# ISP.net
KiCad netlist of a schematic drawn in EAGLE
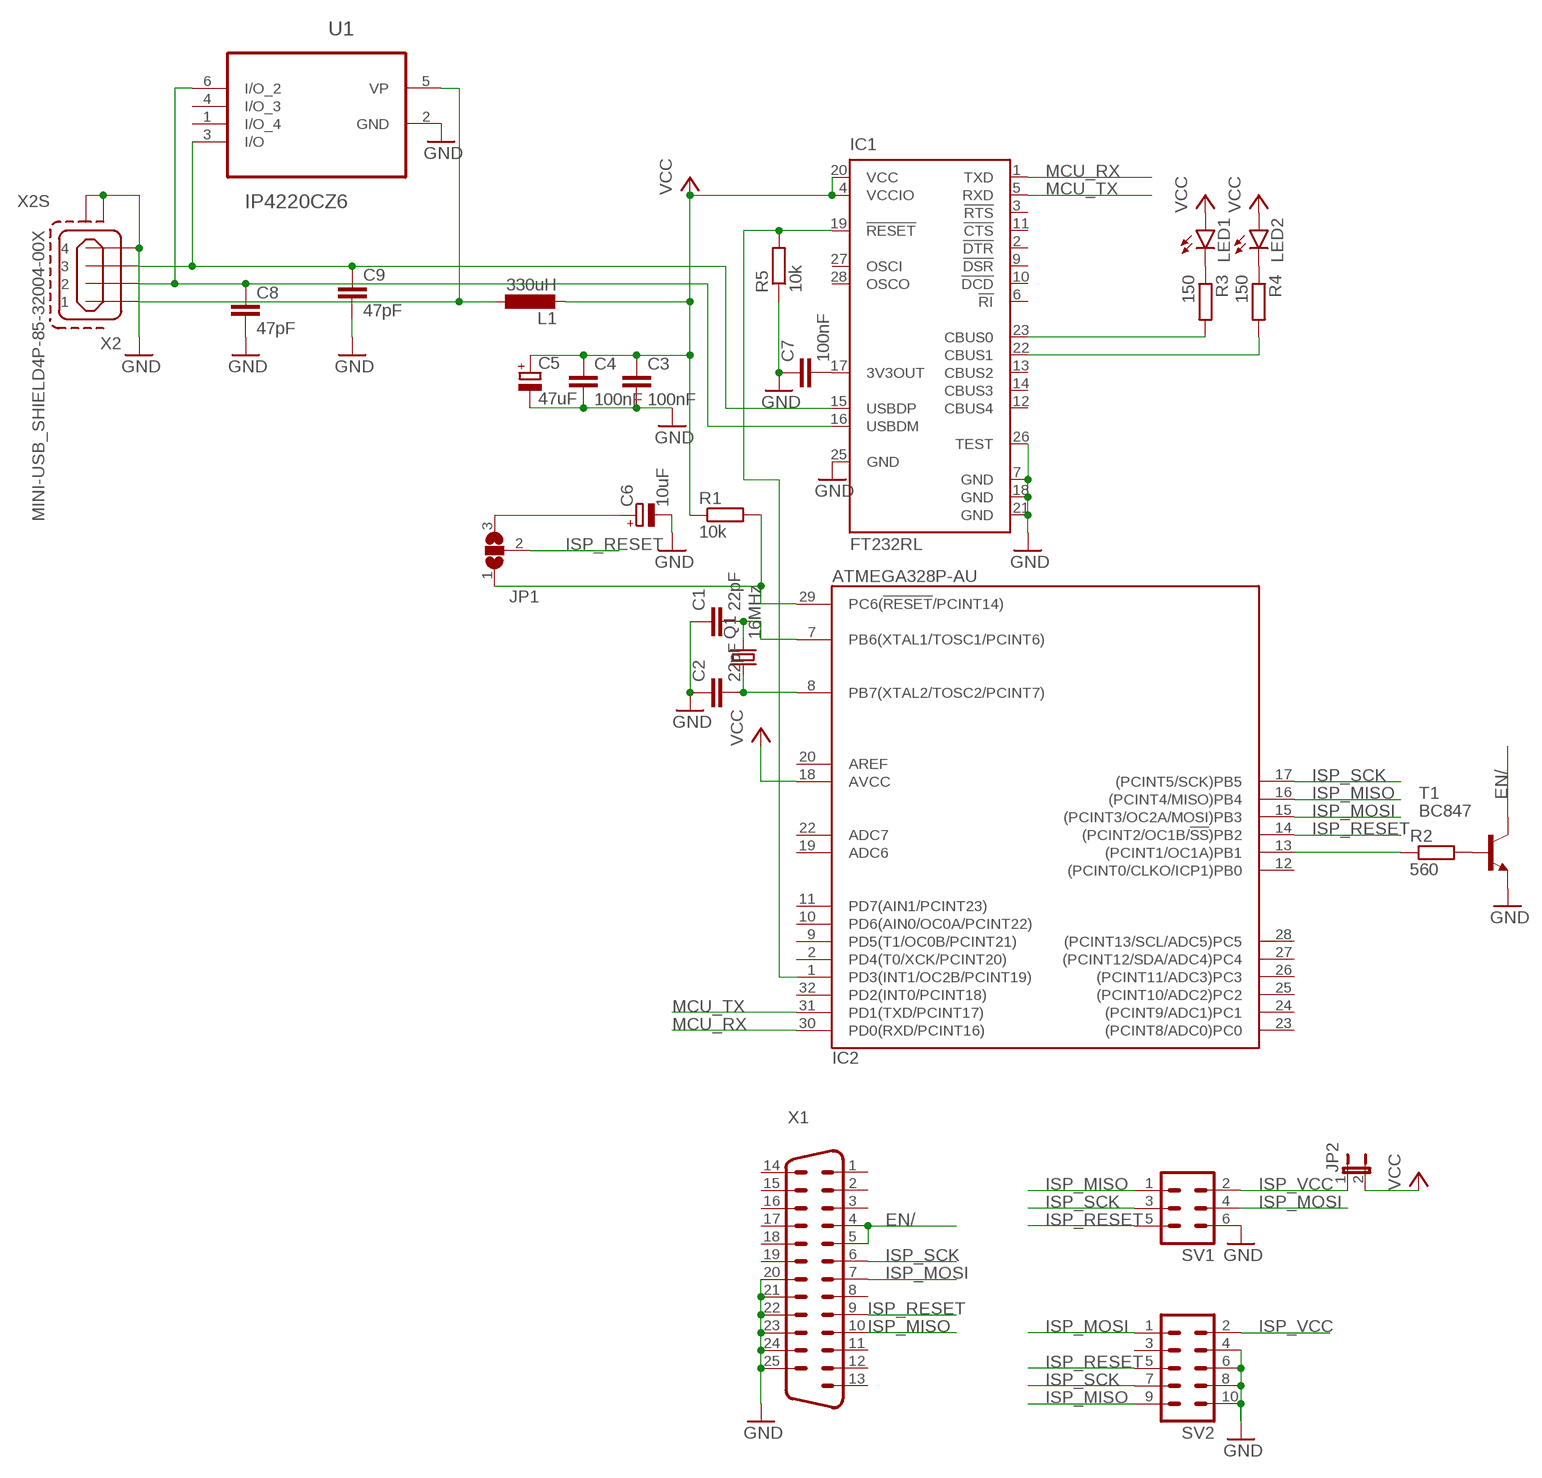
[diagram p0: schematic, sheet 1]

(export (version "E")
  (design (tool "Eeschema 10.0.6"))
  (components
    (comp (ref "C1")
      (value "22pF")
      (footprint "eagle-import:C0805")
      (libsource (lib "eagle-import") (part "C-EUC0805"))
    )
    (comp (ref "C2")
      (value "22pF")
      (footprint "eagle-import:C0805")
      (libsource (lib "eagle-import") (part "C-EUC0805"))
    )
    (comp (ref "C3")
      (value "100nF")
      (footprint "eagle-import:C0805")
      (libsource (lib "eagle-import") (part "C-EUC0805"))
    )
    (comp (ref "C4")
      (value "100nF")
      (footprint "eagle-import:C0805")
      (libsource (lib "eagle-import") (part "C-EUC0805"))
    )
    (comp (ref "C5")
      (value "47uF")
      (footprint "eagle-import:PANASONIC_D")
      (libsource (lib "eagle-import") (part "CPOL-EUD"))
    )
    (comp (ref "C6")
      (value "10uF")
      (footprint "eagle-import:PANASONIC_C")
      (libsource (lib "eagle-import") (part "CPOL-EUC"))
    )
    (comp (ref "C7")
      (value "100nF")
      (footprint "eagle-import:C0805")
      (libsource (lib "eagle-import") (part "C-EUC0805"))
    )
    (comp (ref "C8")
      (value "47pF")
      (footprint "eagle-import:C0805")
      (libsource (lib "eagle-import") (part "C-EUC0805"))
    )
    (comp (ref "C9")
      (value "47pF")
      (footprint "eagle-import:C0805")
      (libsource (lib "eagle-import") (part "C-EUC0805"))
    )
    (comp (ref "IC1")
      (value "FT232RL")
      (footprint "eagle-import:SSOP28")
      (libsource (lib "eagle-import") (part "FT232RL"))
    )
    (comp (ref "IC2")
      (value "ATMEGA328P-AU")
      (footprint "eagle-import:QFP32_7X7_0.80")
      (libsource (lib "eagle-import") (part "ATMEGA8P-AU32"))
    )
    (comp (ref "JP1")
      (value "SJ2W")
      (footprint "eagle-import:SJ_2")
      (libsource (lib "eagle-import") (part "SJ2W"))
    )
    (comp (ref "JP2")
      (value "JP1E")
      (footprint "eagle-import:JP1")
      (libsource (lib "eagle-import") (part "JP1E"))
    )
    (comp (ref "L1")
      (value "330uH")
      (footprint "eagle-import:L1812")
      (libsource (lib "eagle-import") (part "L-EUL1812"))
    )
    (comp (ref "LED1")
      (value "LEDCHIPLED_1206")
      (footprint "eagle-import:CHIPLED_1206")
      (libsource (lib "eagle-import") (part "LEDCHIPLED_1206"))
    )
    (comp (ref "LED2")
      (value "LEDCHIPLED_1206")
      (footprint "eagle-import:CHIPLED_1206")
      (libsource (lib "eagle-import") (part "LEDCHIPLED_1206"))
    )
    (comp (ref "Q1")
      (value "16MHz")
      (footprint "eagle-import:HC49UP")
      (libsource (lib "eagle-import") (part "CRYSTALHC49UP"))
    )
    (comp (ref "R1")
      (value "10k")
      (footprint "eagle-import:R0805")
      (libsource (lib "eagle-import") (part "R-EU_R0805"))
    )
    (comp (ref "R2")
      (value "560")
      (footprint "eagle-import:R0805")
      (libsource (lib "eagle-import") (part "R-EU_R0805"))
    )
    (comp (ref "R3")
      (value "150")
      (footprint "eagle-import:R0805")
      (libsource (lib "eagle-import") (part "R-EU_R0805"))
    )
    (comp (ref "R4")
      (value "150")
      (footprint "eagle-import:R0805")
      (libsource (lib "eagle-import") (part "R-EU_R0805"))
    )
    (comp (ref "R5")
      (value "10k")
      (footprint "eagle-import:R0805")
      (libsource (lib "eagle-import") (part "R-EU_R0805"))
    )
    (comp (ref "SV1")
      (value "ML6")
      (footprint "eagle-import:ML6")
      (libsource (lib "eagle-import") (part "ML6"))
    )
    (comp (ref "SV2")
      (value "ML10")
      (footprint "eagle-import:ML10")
      (libsource (lib "eagle-import") (part "ML10"))
    )
    (comp (ref "T1")
      (value "BC847")
      (footprint "eagle-import:SOT23")
      (libsource (lib "eagle-import") (part "BC847"))
    )
    (comp (ref "U1")
      (value "IP4220CZ6")
      (footprint "eagle-import:SOT95P275X110-6N")
      (libsource (lib "eagle-import") (part "IP4220CZ6"))
    )
    (comp (ref "X1")
      (value "M25HP")
      (footprint "eagle-import:M25HP")
      (libsource (lib "eagle-import") (part "M25HP"))
    )
    (comp (ref "X2")
      (value "MINI-USB_SHIELD4P-85-32004-00X")
      (footprint "eagle-import:85-32004-00X")
      (libsource (lib "eagle-import") (part "MINI-USB_SHIELD4P-85-32004-00X"))
    )
  )
  (nets
    (net (code "1") (name "/EN{slash}") (class "Default")
      (node (ref "T1") (pin "3") (pinfunction "C_3") (pintype "passive"))
      (node (ref "X1") (pin "4") (pinfunction "4_4") (pintype "passive"))
      (node (ref "X1") (pin "5") (pinfunction "5_5") (pintype "passive"))
    )
    (net (code "2") (name "/ISP_MISO") (class "Default")
      (node (ref "IC2") (pin "16") (pinfunction "(PCINT4/MISO)PB4_16") (pintype "bidirectional"))
      (node (ref "SV1") (pin "1") (pinfunction "1_1") (pintype "passive"))
      (node (ref "SV2") (pin "9") (pinfunction "9_9") (pintype "passive"))
      (node (ref "X1") (pin "10") (pinfunction "10_10") (pintype "passive"))
    )
    (net (code "3") (name "/ISP_MOSI") (class "Default")
      (node (ref "IC2") (pin "15") (pinfunction "(PCINT3/OC2A/MOSI)PB3_15") (pintype "bidirectional"))
      (node (ref "SV1") (pin "4") (pinfunction "4_4") (pintype "passive"))
      (node (ref "SV2") (pin "1") (pinfunction "1_1") (pintype "passive"))
      (node (ref "X1") (pin "7") (pinfunction "7_7") (pintype "passive"))
    )
    (net (code "4") (name "/ISP_RESET") (class "Default")
      (node (ref "IC2") (pin "14") (pinfunction "(PCINT2/OC1B/~{SS})PB2_14") (pintype "bidirectional"))
      (node (ref "JP1") (pin "2") (pinfunction "2_2") (pintype "passive"))
      (node (ref "SV1") (pin "5") (pinfunction "5_5") (pintype "passive"))
      (node (ref "SV2") (pin "5") (pinfunction "5_5") (pintype "passive"))
      (node (ref "X1") (pin "9") (pinfunction "9_9") (pintype "passive"))
    )
    (net (code "5") (name "/ISP_SCK") (class "Default")
      (node (ref "IC2") (pin "17") (pinfunction "(PCINT5/SCK)PB5_17") (pintype "bidirectional"))
      (node (ref "SV1") (pin "3") (pinfunction "3_3") (pintype "passive"))
      (node (ref "SV2") (pin "7") (pinfunction "7_7") (pintype "passive"))
      (node (ref "X1") (pin "6") (pinfunction "6_6") (pintype "passive"))
    )
    (net (code "6") (name "/ISP_VCC") (class "Default")
      (node (ref "JP2") (pin "1") (pinfunction "1_1") (pintype "passive"))
      (node (ref "SV1") (pin "2") (pinfunction "2_2") (pintype "passive"))
      (node (ref "SV2") (pin "2") (pinfunction "2_2") (pintype "passive"))
    )
    (net (code "7") (name "/MCU_RX") (class "Default")
      (node (ref "IC1") (pin "1") (pinfunction "TXD_1") (pintype "output"))
      (node (ref "IC2") (pin "30") (pinfunction "PD0(RXD/PCINT16)_30") (pintype "bidirectional"))
    )
    (net (code "8") (name "/MCU_TX") (class "Default")
      (node (ref "IC1") (pin "5") (pinfunction "RXD_5") (pintype "input"))
      (node (ref "IC2") (pin "31") (pinfunction "PD1(TXD/PCINT17)_31") (pintype "bidirectional"))
    )
    (net (code "9") (name "GND") (class "Default")
      (node (ref "C1") (pin "1") (pinfunction "1_1") (pintype "passive"))
      (node (ref "C2") (pin "1") (pinfunction "1_1") (pintype "passive"))
      (node (ref "C3") (pin "2") (pinfunction "2_2") (pintype "passive"))
      (node (ref "C4") (pin "2") (pinfunction "2_2") (pintype "passive"))
      (node (ref "C5") (pin "-") (pinfunction "-_-") (pintype "passive"))
      (node (ref "C6") (pin "-") (pinfunction "-_-") (pintype "passive"))
      (node (ref "C7") (pin "1") (pinfunction "1_1") (pintype "passive"))
      (node (ref "C8") (pin "2") (pinfunction "2_2") (pintype "passive"))
      (node (ref "C9") (pin "2") (pinfunction "2_2") (pintype "passive"))
      (node (ref "IC1") (pin "18") (pinfunction "GND_18") (pintype "power_in"))
      (node (ref "IC1") (pin "21") (pinfunction "GND_21") (pintype "power_in"))
      (node (ref "IC1") (pin "25") (pinfunction "GND_25") (pintype "power_in"))
      (node (ref "IC1") (pin "26") (pinfunction "TEST_26") (pintype "input"))
      (node (ref "IC1") (pin "7") (pinfunction "GND_7") (pintype "power_in"))
      (node (ref "R5") (pin "1") (pinfunction "1_1") (pintype "passive"))
      (node (ref "SV1") (pin "6") (pinfunction "6_6") (pintype "passive"))
      (node (ref "SV2") (pin "10") (pinfunction "10_10") (pintype "passive"))
      (node (ref "SV2") (pin "4") (pinfunction "4_4") (pintype "passive"))
      (node (ref "SV2") (pin "6") (pinfunction "6_6") (pintype "passive"))
      (node (ref "SV2") (pin "8") (pinfunction "8_8") (pintype "passive"))
      (node (ref "T1") (pin "2") (pinfunction "E_2") (pintype "passive"))
      (node (ref "U1") (pin "2") (pinfunction "GND_2") (pintype "passive"))
      (node (ref "X1") (pin "20") (pinfunction "20_20") (pintype "passive"))
      (node (ref "X1") (pin "21") (pinfunction "21_21") (pintype "passive"))
      (node (ref "X1") (pin "22") (pinfunction "22_22") (pintype "passive"))
      (node (ref "X1") (pin "23") (pinfunction "23_23") (pintype "passive"))
      (node (ref "X1") (pin "24") (pinfunction "24_24") (pintype "passive"))
      (node (ref "X1") (pin "25") (pinfunction "25_25") (pintype "passive"))
      (node (ref "X2") (pin "4") (pinfunction "4_4") (pintype "passive"))
      (node (ref "X2") (pin "M1") (pinfunction "S1_M1") (pintype "passive"))
      (node (ref "X2") (pin "M2") (pinfunction "S2_M2") (pintype "passive"))
    )
    (net (code "10") (name "Net-(C6-Pad+)") (class "Default")
      (node (ref "C6") (pin "+") (pinfunction "+_+") (pintype "passive"))
      (node (ref "JP1") (pin "3") (pinfunction "3_3") (pintype "passive"))
    )
    (net (code "11") (name "Net-(IC1-3V3OUT)") (class "Default")
      (node (ref "C7") (pin "2") (pinfunction "2_2") (pintype "passive"))
      (node (ref "IC1") (pin "17") (pinfunction "3V3OUT_17") (pintype "output"))
    )
    (net (code "12") (name "Net-(IC1-CBUS0)") (class "Default")
      (node (ref "IC1") (pin "23") (pinfunction "CBUS0_23") (pintype "bidirectional"))
      (node (ref "R3") (pin "2") (pinfunction "2_2") (pintype "passive"))
    )
    (net (code "13") (name "Net-(IC1-CBUS1)") (class "Default")
      (node (ref "IC1") (pin "22") (pinfunction "CBUS1_22") (pintype "bidirectional"))
      (node (ref "R4") (pin "2") (pinfunction "2_2") (pintype "passive"))
    )
    (net (code "14") (name "Net-(IC1-USBDM)") (class "Default")
      (node (ref "C8") (pin "1") (pinfunction "1_1") (pintype "passive"))
      (node (ref "IC1") (pin "16") (pinfunction "USBDM_16") (pintype "bidirectional"))
      (node (ref "U1") (pin "6") (pinfunction "I/O_2_6") (pintype "bidirectional"))
      (node (ref "X2") (pin "2") (pinfunction "2_2") (pintype "passive"))
    )
    (net (code "15") (name "Net-(IC1-USBDP)") (class "Default")
      (node (ref "C9") (pin "1") (pinfunction "1_1") (pintype "passive"))
      (node (ref "IC1") (pin "15") (pinfunction "USBDP_15") (pintype "bidirectional"))
      (node (ref "U1") (pin "3") (pinfunction "I/O_3") (pintype "bidirectional"))
      (node (ref "X2") (pin "3") (pinfunction "3_3") (pintype "passive"))
    )
    (net (code "16") (name "Net-(IC1-~{RESET})") (class "Default")
      (node (ref "IC1") (pin "19") (pinfunction "~{RESET}_19") (pintype "input"))
      (node (ref "IC2") (pin "1") (pinfunction "PD3(INT1/OC2B/PCINT19)_1") (pintype "bidirectional"))
      (node (ref "R5") (pin "2") (pinfunction "2_2") (pintype "passive"))
    )
    (net (code "17") (name "Net-(IC2A-(PCINT1{slash}OC1A)PB1)") (class "Default")
      (node (ref "IC2") (pin "13") (pinfunction "(PCINT1/OC1A)PB1_13") (pintype "bidirectional"))
      (node (ref "R2") (pin "1") (pinfunction "1_1") (pintype "passive"))
    )
    (net (code "18") (name "Net-(IC2A-PB6(XTAL1{slash}TOSC1{slash}PCINT6))") (class "Default")
      (node (ref "C1") (pin "2") (pinfunction "2_2") (pintype "passive"))
      (node (ref "IC2") (pin "7") (pinfunction "PB6(XTAL1/TOSC1/PCINT6)_7") (pintype "bidirectional"))
      (node (ref "Q1") (pin "2") (pinfunction "2_2") (pintype "passive"))
    )
    (net (code "19") (name "Net-(IC2A-PB7(XTAL2{slash}TOSC2{slash}PCINT7))") (class "Default")
      (node (ref "C2") (pin "2") (pinfunction "2_2") (pintype "passive"))
      (node (ref "IC2") (pin "8") (pinfunction "PB7(XTAL2/TOSC2/PCINT7)_8") (pintype "bidirectional"))
      (node (ref "Q1") (pin "1") (pinfunction "1_1") (pintype "passive"))
    )
    (net (code "20") (name "Net-(IC2A-PC6(~{RESET}{slash}PCINT14))") (class "Default")
      (node (ref "IC2") (pin "29") (pinfunction "PC6(~{RESET}/PCINT14)_29") (pintype "bidirectional"))
      (node (ref "JP1") (pin "1") (pinfunction "1_1") (pintype "passive"))
      (node (ref "R1") (pin "2") (pinfunction "2_2") (pintype "passive"))
    )
    (net (code "21") (name "Net-(LED1-PadC)") (class "Default")
      (node (ref "LED1") (pin "C") (pinfunction "C_C") (pintype "passive"))
      (node (ref "R3") (pin "1") (pinfunction "1_1") (pintype "passive"))
    )
    (net (code "22") (name "Net-(LED2-PadC)") (class "Default")
      (node (ref "LED2") (pin "C") (pinfunction "C_C") (pintype "passive"))
      (node (ref "R4") (pin "1") (pinfunction "1_1") (pintype "passive"))
    )
    (net (code "23") (name "Net-(T1-B)") (class "Default")
      (node (ref "R2") (pin "2") (pinfunction "2_2") (pintype "passive"))
      (node (ref "T1") (pin "1") (pinfunction "B_1") (pintype "passive"))
    )
    (net (code "24") (name "Net-(U1-VP)") (class "Default")
      (node (ref "L1") (pin "1") (pinfunction "1_1") (pintype "passive"))
      (node (ref "U1") (pin "5") (pinfunction "VP_5") (pintype "power_in"))
      (node (ref "X2") (pin "1") (pinfunction "1_1") (pintype "passive"))
    )
    (net (code "25") (name "VCC") (class "Default")
      (node (ref "C3") (pin "1") (pinfunction "1_1") (pintype "passive"))
      (node (ref "C4") (pin "1") (pinfunction "1_1") (pintype "passive"))
      (node (ref "C5") (pin "+") (pinfunction "+_+") (pintype "passive"))
      (node (ref "IC1") (pin "20") (pinfunction "VCC_20") (pintype "power_in"))
      (node (ref "IC1") (pin "4") (pinfunction "VCCIO_4") (pintype "power_in"))
      (node (ref "IC2") (pin "18") (pinfunction "AVCC_18") (pintype "power_in"))
      (node (ref "JP2") (pin "2") (pinfunction "2_2") (pintype "passive"))
      (node (ref "L1") (pin "2") (pinfunction "2_2") (pintype "passive"))
      (node (ref "LED1") (pin "A") (pinfunction "A_A") (pintype "passive"))
      (node (ref "LED2") (pin "A") (pinfunction "A_A") (pintype "passive"))
      (node (ref "R1") (pin "1") (pinfunction "1_1") (pintype "passive"))
    )
    (net (code "26") (name "unconnected-(IC1-CBUS2-Pad13)") (class "Default")
      (node (ref "IC1") (pin "13") (pinfunction "CBUS2_13") (pintype "bidirectional"))
    )
    (net (code "27") (name "unconnected-(IC1-CBUS3-Pad14)") (class "Default")
      (node (ref "IC1") (pin "14") (pinfunction "CBUS3_14") (pintype "bidirectional"))
    )
    (net (code "28") (name "unconnected-(IC1-CBUS4-Pad12)") (class "Default")
      (node (ref "IC1") (pin "12") (pinfunction "CBUS4_12") (pintype "bidirectional"))
    )
    (net (code "29") (name "unconnected-(IC1-OSCI-Pad27)") (class "Default")
      (node (ref "IC1") (pin "27") (pinfunction "OSCI_27") (pintype "input"))
    )
    (net (code "30") (name "unconnected-(IC1-OSCO-Pad28)") (class "Default")
      (node (ref "IC1") (pin "28") (pinfunction "OSCO_28") (pintype "output"))
    )
    (net (code "31") (name "unconnected-(IC1-~{CTS}-Pad11)") (class "Default")
      (node (ref "IC1") (pin "11") (pinfunction "~{CTS}_11") (pintype "input"))
    )
    (net (code "32") (name "unconnected-(IC1-~{DCD}-Pad10)") (class "Default")
      (node (ref "IC1") (pin "10") (pinfunction "~{DCD}_10") (pintype "input"))
    )
    (net (code "33") (name "unconnected-(IC1-~{DSR}-Pad9)") (class "Default")
      (node (ref "IC1") (pin "9") (pinfunction "~{DSR}_9") (pintype "input"))
    )
    (net (code "34") (name "unconnected-(IC1-~{DTR}-Pad2)") (class "Default")
      (node (ref "IC1") (pin "2") (pinfunction "~{DTR}_2") (pintype "output"))
    )
    (net (code "35") (name "unconnected-(IC1-~{RI}-Pad6)") (class "Default")
      (node (ref "IC1") (pin "6") (pinfunction "~{RI}_6") (pintype "input"))
    )
    (net (code "36") (name "unconnected-(IC1-~{RTS}-Pad3)") (class "Default")
      (node (ref "IC1") (pin "3") (pinfunction "~{RTS}_3") (pintype "output"))
    )
    (net (code "37") (name "unconnected-(IC2A-(PCINT0{slash}CLKO{slash}ICP1)PB0-Pad12)") (class "Default")
      (node (ref "IC2") (pin "12") (pinfunction "(PCINT0/CLKO/ICP1)PB0_12") (pintype "bidirectional"))
    )
    (net (code "38") (name "unconnected-(IC2A-(PCINT8{slash}ADC0)PC0-Pad23)") (class "Default")
      (node (ref "IC2") (pin "23") (pinfunction "(PCINT8/ADC0)PC0_23") (pintype "bidirectional"))
    )
    (net (code "39") (name "unconnected-(IC2A-(PCINT9{slash}ADC1)PC1-Pad24)") (class "Default")
      (node (ref "IC2") (pin "24") (pinfunction "(PCINT9/ADC1)PC1_24") (pintype "bidirectional"))
    )
    (net (code "40") (name "unconnected-(IC2A-(PCINT10{slash}ADC2)PC2-Pad25)") (class "Default")
      (node (ref "IC2") (pin "25") (pinfunction "(PCINT10/ADC2)PC2_25") (pintype "bidirectional"))
    )
    (net (code "41") (name "unconnected-(IC2A-(PCINT11{slash}ADC3)PC3-Pad26)") (class "Default")
      (node (ref "IC2") (pin "26") (pinfunction "(PCINT11/ADC3)PC3_26") (pintype "bidirectional"))
    )
    (net (code "42") (name "unconnected-(IC2A-(PCINT12{slash}SDA{slash}ADC4)PC4-Pad27)") (class "Default")
      (node (ref "IC2") (pin "27") (pinfunction "(PCINT12/SDA/ADC4)PC4_27") (pintype "bidirectional"))
    )
    (net (code "43") (name "unconnected-(IC2A-(PCINT13{slash}SCL{slash}ADC5)PC5-Pad28)") (class "Default")
      (node (ref "IC2") (pin "28") (pinfunction "(PCINT13/SCL/ADC5)PC5_28") (pintype "bidirectional"))
    )
    (net (code "44") (name "unconnected-(IC2A-ADC6-Pad19)") (class "Default")
      (node (ref "IC2") (pin "19") (pinfunction "ADC6_19") (pintype "bidirectional"))
    )
    (net (code "45") (name "unconnected-(IC2A-ADC7-Pad22)") (class "Default")
      (node (ref "IC2") (pin "22") (pinfunction "ADC7_22") (pintype "bidirectional"))
    )
    (net (code "46") (name "unconnected-(IC2A-AREF-Pad20)") (class "Default")
      (node (ref "IC2") (pin "20") (pinfunction "AREF_20") (pintype "passive"))
    )
    (net (code "47") (name "unconnected-(IC2A-PD2(INT0{slash}PCINT18)-Pad32)") (class "Default")
      (node (ref "IC2") (pin "32") (pinfunction "PD2(INT0/PCINT18)_32") (pintype "bidirectional"))
    )
    (net (code "48") (name "unconnected-(IC2A-PD4(T0{slash}XCK{slash}PCINT20)-Pad2)") (class "Default")
      (node (ref "IC2") (pin "2") (pinfunction "PD4(T0/XCK/PCINT20)_2") (pintype "bidirectional"))
    )
    (net (code "49") (name "unconnected-(IC2A-PD5(T1{slash}OC0B{slash}PCINT21)-Pad9)") (class "Default")
      (node (ref "IC2") (pin "9") (pinfunction "PD5(T1/OC0B/PCINT21)_9") (pintype "bidirectional"))
    )
    (net (code "50") (name "unconnected-(IC2A-PD6(AIN0{slash}OC0A{slash}PCINT22)-Pad10)") (class "Default")
      (node (ref "IC2") (pin "10") (pinfunction "PD6(AIN0/OC0A/PCINT22)_10") (pintype "bidirectional"))
    )
    (net (code "51") (name "unconnected-(IC2A-PD7(AIN1{slash}PCINT23)-Pad11)") (class "Default")
      (node (ref "IC2") (pin "11") (pinfunction "PD7(AIN1/PCINT23)_11") (pintype "bidirectional"))
    )
    (net (code "52") (name "unconnected-(SV2-Pad3)") (class "Default")
      (node (ref "SV2") (pin "3") (pinfunction "3_3") (pintype "passive"))
    )
    (net (code "53") (name "unconnected-(U1-I{slash}O_3-Pad4)") (class "Default")
      (node (ref "U1") (pin "4") (pinfunction "I/O_3_4") (pintype "bidirectional"))
    )
    (net (code "54") (name "unconnected-(U1-I{slash}O_4-Pad1)") (class "Default")
      (node (ref "U1") (pin "1") (pinfunction "I/O_4_1") (pintype "bidirectional"))
    )
    (net (code "55") (name "unconnected-(X1-Pad1)") (class "Default")
      (node (ref "X1") (pin "1") (pinfunction "1_1") (pintype "passive"))
    )
    (net (code "56") (name "unconnected-(X1-Pad2)") (class "Default")
      (node (ref "X1") (pin "2") (pinfunction "2_2") (pintype "passive"))
    )
    (net (code "57") (name "unconnected-(X1-Pad3)") (class "Default")
      (node (ref "X1") (pin "3") (pinfunction "3_3") (pintype "passive"))
    )
    (net (code "58") (name "unconnected-(X1-Pad8)") (class "Default")
      (node (ref "X1") (pin "8") (pinfunction "8_8") (pintype "passive"))
    )
    (net (code "59") (name "unconnected-(X1-Pad11)") (class "Default")
      (node (ref "X1") (pin "11") (pinfunction "11_11") (pintype "passive"))
    )
    (net (code "60") (name "unconnected-(X1-Pad12)") (class "Default")
      (node (ref "X1") (pin "12") (pinfunction "12_12") (pintype "passive"))
    )
    (net (code "61") (name "unconnected-(X1-Pad13)") (class "Default")
      (node (ref "X1") (pin "13") (pinfunction "13_13") (pintype "passive"))
    )
    (net (code "62") (name "unconnected-(X1-Pad14)") (class "Default")
      (node (ref "X1") (pin "14") (pinfunction "14_14") (pintype "passive"))
    )
    (net (code "63") (name "unconnected-(X1-Pad15)") (class "Default")
      (node (ref "X1") (pin "15") (pinfunction "15_15") (pintype "passive"))
    )
    (net (code "64") (name "unconnected-(X1-Pad16)") (class "Default")
      (node (ref "X1") (pin "16") (pinfunction "16_16") (pintype "passive"))
    )
    (net (code "65") (name "unconnected-(X1-Pad17)") (class "Default")
      (node (ref "X1") (pin "17") (pinfunction "17_17") (pintype "passive"))
    )
    (net (code "66") (name "unconnected-(X1-Pad18)") (class "Default")
      (node (ref "X1") (pin "18") (pinfunction "18_18") (pintype "passive"))
    )
    (net (code "67") (name "unconnected-(X1-Pad19)") (class "Default")
      (node (ref "X1") (pin "19") (pinfunction "19_19") (pintype "passive"))
    )
  )
)
